# openSX70_LENS_BELLOWS_V51_20180120.net
KiCad netlist of a schematic drawn in EAGLE
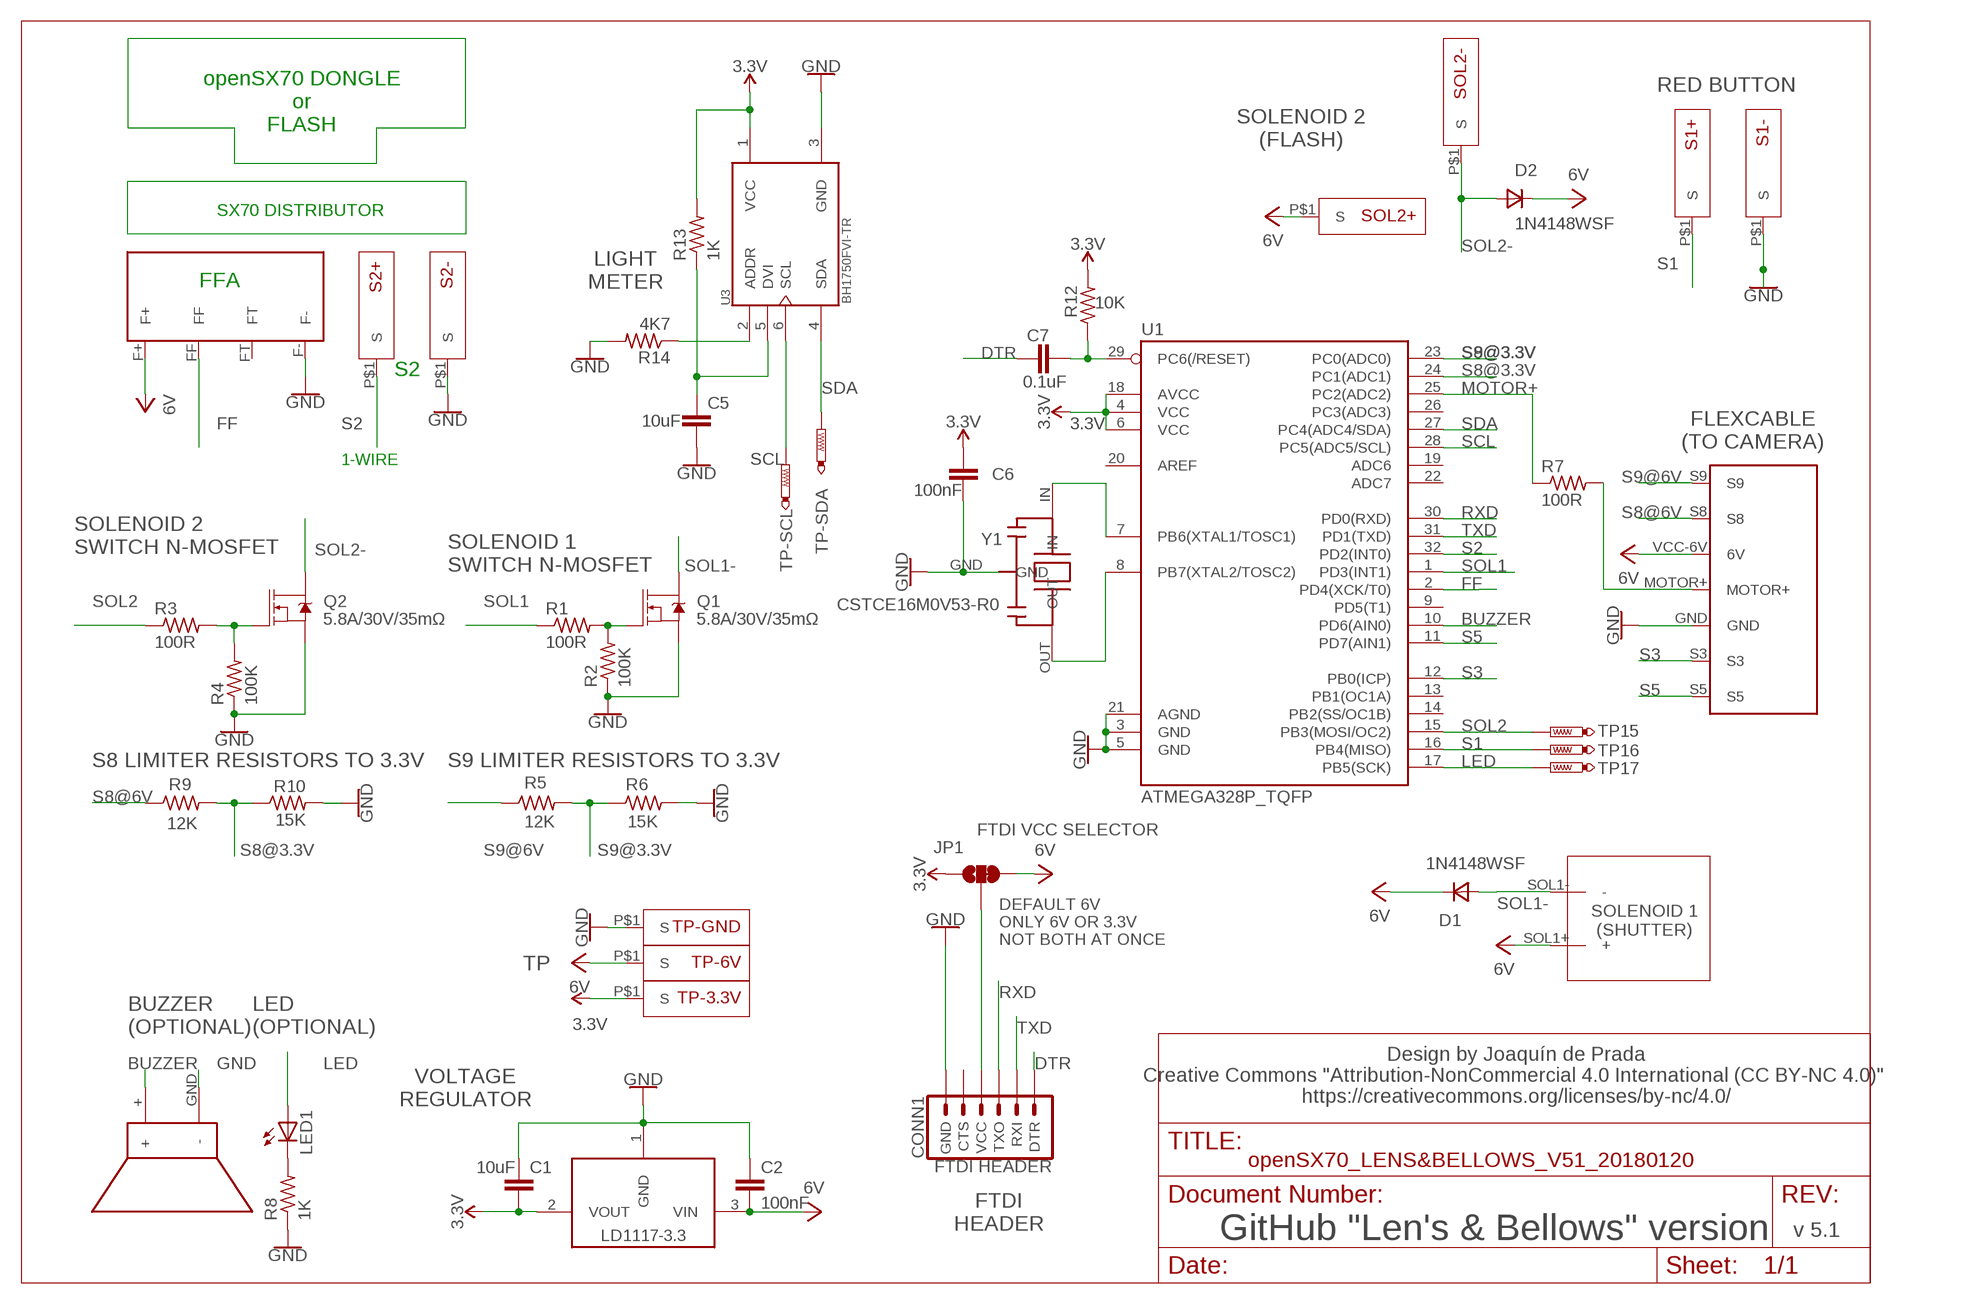
[diagram p0: schematic, sheet 1]

(export (version "E")
  (design (tool "Eeschema 10.0.6"))
  (components
    (comp (ref "BUZZ1")
      (value "CSET8-5G")
      (footprint "eagle-import:CSET8-5G_PACKAGE")
      (libsource (lib "eagle-import") (part "CSET8-5G"))
    )
    (comp (ref "C1")
      (value "10uF")
      (footprint "eagle-import:0603")
      (libsource (lib "eagle-import") (part "10UF-0603-6.3V-20%"))
    )
    (comp (ref "C2")
      (value "100nF")
      (footprint "eagle-import:C0603K")
      (libsource (lib "eagle-import") (part "C-EUC0603K"))
    )
    (comp (ref "C5")
      (value "10uF")
      (footprint "eagle-import:0603")
      (libsource (lib "eagle-import") (part "10UF-0603-6.3V-20%"))
    )
    (comp (ref "C6")
      (value "100nF")
      (footprint "eagle-import:C0603K")
      (libsource (lib "eagle-import") (part "C-EUC0603K"))
    )
    (comp (ref "C7")
      (value "0.1uF")
      (footprint "eagle-import:0603")
      (libsource (lib "eagle-import") (part "0.1UF-0603-25V-(+80/-20%)"))
    )
    (comp (ref "CONN1")
      (value "FTDI HEADER")
      (footprint "eagle-import:1X06")
      (libsource (lib "eagle-import") (part "6_PIN_SERIAL_TARGET"))
    )
    (comp (ref "D1")
      (value "1N4148WSF")
      (footprint "eagle-import:SOD323")
      (fields (field (name "MPN") "CDSOD323-T05C"))
      (libsource (lib "eagle-import") (part "DSOD323"))
    )
    (comp (ref "D2")
      (value "1N4148WSF")
      (footprint "eagle-import:SOD323")
      (fields (field (name "MPN") "CDSOD323-T05C"))
      (libsource (lib "eagle-import") (part "DSOD323"))
    )
    (comp (ref "JP1")
      (value "FTDI VCC SELECTOR")
      (footprint "eagle-import:SMT-JUMPER_3_1-NC_TRACE_SILK")
      (libsource (lib "eagle-import") (part "JUMPER-SMT_3_1-NC_TRACE_SILK"))
    )
    (comp (ref "LD11173.3V")
      (value "LD1117 3.3V")
      (footprint "eagle-import:SOT223")
      (fields (field (name "MF") "Advanced Monolithic Systems") (field (name "MP") "AMS1117-5.0"))
      (libsource (lib "eagle-import") (part "LD1117-3.3"))
    )
    (comp (ref "LED1")
      (value "LEDCHIPLED_0805")
      (footprint "eagle-import:CHIPLED_0805")
      (libsource (lib "eagle-import") (part "LEDCHIPLED_0805"))
    )
    (comp (ref "Q1")
      (value "5.8A/30V/35mΩ")
      (footprint "eagle-import:SOT23-3")
      (libsource (lib "eagle-import") (part "MOSFET-NCH-AO3404A"))
    )
    (comp (ref "Q2")
      (value "5.8A/30V/35mΩ")
      (footprint "eagle-import:SOT23-3")
      (libsource (lib "eagle-import") (part "MOSFET-NCH-AO3404A"))
    )
    (comp (ref "R1")
      (value "100R")
      (footprint "eagle-import:R0603")
      (libsource (lib "eagle-import") (part "R-US_R0603"))
    )
    (comp (ref "R2")
      (value "100K")
      (footprint "eagle-import:R0603")
      (libsource (lib "eagle-import") (part "R-US_R0603"))
    )
    (comp (ref "R3")
      (value "100R")
      (footprint "eagle-import:R0603")
      (libsource (lib "eagle-import") (part "R-US_R0603"))
    )
    (comp (ref "R4")
      (value "100K")
      (footprint "eagle-import:R0603")
      (libsource (lib "eagle-import") (part "R-US_R0603"))
    )
    (comp (ref "R5")
      (value "12K")
      (footprint "eagle-import:R0603")
      (libsource (lib "eagle-import") (part "R-US_R0603"))
    )
    (comp (ref "R6")
      (value "15K")
      (footprint "eagle-import:R0603")
      (libsource (lib "eagle-import") (part "R-US_R0603"))
    )
    (comp (ref "R7")
      (value "100R")
      (footprint "eagle-import:R0603")
      (libsource (lib "eagle-import") (part "R-US_R0603"))
    )
    (comp (ref "R8")
      (value "1K")
      (footprint "eagle-import:R0603")
      (libsource (lib "eagle-import") (part "R-US_R0603"))
    )
    (comp (ref "R9")
      (value "12K")
      (footprint "eagle-import:R0603")
      (libsource (lib "eagle-import") (part "R-US_R0603"))
    )
    (comp (ref "R10")
      (value "15K")
      (footprint "eagle-import:R0603")
      (libsource (lib "eagle-import") (part "R-US_R0603"))
    )
    (comp (ref "R12")
      (value "10K")
      (footprint "eagle-import:R0603")
      (libsource (lib "eagle-import") (part "R-US_R0603"))
    )
    (comp (ref "R13")
      (value "1K")
      (footprint "eagle-import:R0603")
      (libsource (lib "eagle-import") (part "R-US_R0603"))
    )
    (comp (ref "R14")
      (value "4K7")
      (footprint "eagle-import:R0603")
      (libsource (lib "eagle-import") (part "R-US_R0603"))
    )
    (comp (ref "S1+")
      (value "SX70-S-PAD-NEW")
      (footprint "eagle-import:SX70-S-PAD2")
      (libsource (lib "eagle-import") (part "SX70-S-PAD-NEW"))
    )
    (comp (ref "S1-")
      (value "SX70-S-PAD-NEW")
      (footprint "eagle-import:SX70-S-PAD2")
      (libsource (lib "eagle-import") (part "SX70-S-PAD-NEW"))
    )
    (comp (ref "S2+")
      (value "SX70-S-PAD-NEW")
      (footprint "eagle-import:SX70-S-PAD2")
      (libsource (lib "eagle-import") (part "SX70-S-PAD-NEW"))
    )
    (comp (ref "S2-")
      (value "SX70-S-PAD-NEW")
      (footprint "eagle-import:SX70-S-PAD2")
      (libsource (lib "eagle-import") (part "SX70-S-PAD-NEW"))
    )
    (comp (ref "SOL1")
      (value "SX70-SOLENOID1-2PADS")
      (footprint "eagle-import:SX70-SOLENOID1-2")
      (libsource (lib "eagle-import") (part "SX70-SOLENOID1-2PADS"))
    )
    (comp (ref "SOL2+")
      (value "SX70-S-PAD-NEW")
      (footprint "eagle-import:SX70-S-PAD2")
      (libsource (lib "eagle-import") (part "SX70-S-PAD-NEW"))
    )
    (comp (ref "SOL2-")
      (value "SX70-S-PAD-NEW")
      (footprint "eagle-import:SX70-S-PAD2")
      (libsource (lib "eagle-import") (part "SX70-S-PAD-NEW"))
    )
    (comp (ref "TP-3.3V")
      (value "SX70-S-PAD-NEW")
      (footprint "eagle-import:SX70-S-PAD2")
      (libsource (lib "eagle-import") (part "SX70-S-PAD-NEW"))
    )
    (comp (ref "TP-6V")
      (value "SX70-S-PAD-NEW")
      (footprint "eagle-import:SX70-S-PAD2")
      (libsource (lib "eagle-import") (part "SX70-S-PAD-NEW"))
    )
    (comp (ref "TP-GND")
      (value "SX70-S-PAD-NEW")
      (footprint "eagle-import:SX70-S-PAD2")
      (libsource (lib "eagle-import") (part "SX70-S-PAD-NEW"))
    )
    (comp (ref "TP-SCL")
      (value "PTR1TP08R")
      (footprint "eagle-import:TP08R")
      (libsource (lib "eagle-import") (part "PTR1TP08R"))
    )
    (comp (ref "TP-SDA")
      (value "PTR1TP08R")
      (footprint "eagle-import:TP08R")
      (libsource (lib "eagle-import") (part "PTR1TP08R"))
    )
    (comp (ref "TP15")
      (value "PTR1TP08R")
      (footprint "eagle-import:TP08R")
      (libsource (lib "eagle-import") (part "PTR1TP08R"))
    )
    (comp (ref "TP16")
      (value "PTR1TP08R")
      (footprint "eagle-import:TP08R")
      (libsource (lib "eagle-import") (part "PTR1TP08R"))
    )
    (comp (ref "TP17")
      (value "PTR1TP08R")
      (footprint "eagle-import:TP08R")
      (libsource (lib "eagle-import") (part "PTR1TP08R"))
    )
    (comp (ref "U$1")
      (value "SX70-7-PAD")
      (footprint "eagle-import:SX70-7-PAD")
      (libsource (lib "eagle-import") (part "SX70-7-PAD"))
    )
    (comp (ref "U$2")
      (value "FFA")
      (footprint "eagle-import:FFA-PAD-PACKAGE")
      (libsource (lib "eagle-import") (part "SX70-FFA-PAD"))
    )
    (comp (ref "U1")
      (value "ATMEGA328P_TQFP")
      (footprint "eagle-import:TQFP32-08")
      (libsource (lib "eagle-import") (part "ATMEGA328P_TQFP"))
    )
    (comp (ref "U3")
      (value "BH1750FVI-TR")
      (footprint "eagle-import:SOTFL50P300X75-6N")
      (fields (field (name "MF") "Rohm"))
      (libsource (lib "eagle-import") (part "BH1750FVI-TR"))
    )
    (comp (ref "Y1")
      (value "CSTCE16M0V53-R0")
      (footprint "eagle-import:CFP95P160X100-3N")
      (fields (field (name "MF") "Murata"))
      (libsource (lib "eagle-import") (part "CSTCE16M0V53-R0"))
    )
  )
  (nets
    (net (code "1") (name "/BUZZER") (class "Default")
      (node (ref "BUZZ1") (pin "+") (pinfunction "+_+") (pintype "bidirectional"))
      (node (ref "U1") (pin "10") (pinfunction "PD6(AIN0)_10") (pintype "bidirectional"))
    )
    (net (code "2") (name "/DTR") (class "Default")
      (node (ref "C7") (pin "1") (pinfunction "1_1") (pintype "passive"))
      (node (ref "CONN1") (pin "1") (pinfunction "DTR_1") (pintype "passive"))
    )
    (net (code "3") (name "/FF") (class "Default")
      (node (ref "U$2") (pin "FF") (pinfunction "FF_FF") (pintype "bidirectional"))
      (node (ref "U1") (pin "2") (pinfunction "PD4(XCK/T0)_2") (pintype "bidirectional"))
    )
    (net (code "4") (name "/LED") (class "Default")
      (node (ref "LED1") (pin "A") (pinfunction "A_A") (pintype "passive"))
      (node (ref "TP17") (pin "TP") (pinfunction "TP_TP") (pintype "input"))
      (node (ref "U1") (pin "17") (pinfunction "PB5(SCK)_17") (pintype "bidirectional"))
    )
    (net (code "5") (name "/MOTOR+") (class "Default")
      (node (ref "R7") (pin "1") (pinfunction "1_1") (pintype "passive"))
      (node (ref "U1") (pin "25") (pinfunction "PC2(ADC2)_25") (pintype "bidirectional"))
    )
    (net (code "6") (name "/RXD") (class "Default")
      (node (ref "CONN1") (pin "3") (pinfunction "TXO_3") (pintype "passive"))
      (node (ref "U1") (pin "30") (pinfunction "PD0(RXD)_30") (pintype "bidirectional"))
    )
    (net (code "7") (name "/S1") (class "Default")
      (node (ref "S1+") (pin "P$1") (pinfunction "S_P$1") (pintype "bidirectional"))
      (node (ref "TP16") (pin "TP") (pinfunction "TP_TP") (pintype "input"))
      (node (ref "U1") (pin "16") (pinfunction "PB4(MISO)_16") (pintype "bidirectional"))
    )
    (net (code "8") (name "/S2") (class "Default")
      (node (ref "S2+") (pin "P$1") (pinfunction "S_P$1") (pintype "bidirectional"))
      (node (ref "U1") (pin "32") (pinfunction "PD2(INT0)_32") (pintype "bidirectional"))
    )
    (net (code "9") (name "/S3") (class "Default")
      (node (ref "U$1") (pin "S3") (pinfunction "S3_S3") (pintype "bidirectional"))
      (node (ref "U1") (pin "12") (pinfunction "PB0(ICP)_12") (pintype "bidirectional"))
    )
    (net (code "10") (name "/S5") (class "Default")
      (node (ref "U$1") (pin "S5") (pinfunction "S5_S5") (pintype "bidirectional"))
      (node (ref "U1") (pin "11") (pinfunction "PD7(AIN1)_11") (pintype "bidirectional"))
    )
    (net (code "11") (name "/S8@3.3V") (class "Default")
      (node (ref "R10") (pin "1") (pinfunction "1_1") (pintype "passive"))
      (node (ref "R9") (pin "2") (pinfunction "2_2") (pintype "passive"))
      (node (ref "U1") (pin "24") (pinfunction "PC1(ADC1)_24") (pintype "bidirectional"))
    )
    (net (code "12") (name "/S8@6V") (class "Default")
      (node (ref "R9") (pin "1") (pinfunction "1_1") (pintype "passive"))
      (node (ref "U$1") (pin "S8") (pinfunction "S8_S8") (pintype "bidirectional"))
    )
    (net (code "13") (name "/S9@3.3V") (class "Default")
      (node (ref "R5") (pin "2") (pinfunction "2_2") (pintype "passive"))
      (node (ref "R6") (pin "1") (pinfunction "1_1") (pintype "passive"))
      (node (ref "U1") (pin "23") (pinfunction "PC0(ADC0)_23") (pintype "bidirectional"))
    )
    (net (code "14") (name "/S9@6V") (class "Default")
      (node (ref "R5") (pin "1") (pinfunction "1_1") (pintype "passive"))
      (node (ref "U$1") (pin "S9") (pinfunction "S9_S9") (pintype "bidirectional"))
    )
    (net (code "15") (name "/SCL") (class "Default")
      (node (ref "TP-SCL") (pin "TP") (pinfunction "TP_TP") (pintype "input"))
      (node (ref "U1") (pin "28") (pinfunction "PC5(ADC5/SCL)_28") (pintype "bidirectional"))
      (node (ref "U3") (pin "6") (pinfunction "SCL_6") (pintype "input"))
    )
    (net (code "16") (name "/SDA") (class "Default")
      (node (ref "TP-SDA") (pin "TP") (pinfunction "TP_TP") (pintype "input"))
      (node (ref "U1") (pin "27") (pinfunction "PC4(ADC4/SDA)_27") (pintype "bidirectional"))
      (node (ref "U3") (pin "4") (pinfunction "SDA_4") (pintype "bidirectional"))
    )
    (net (code "17") (name "/SOL1") (class "Default")
      (node (ref "R1") (pin "1") (pinfunction "1_1") (pintype "passive"))
      (node (ref "U1") (pin "1") (pinfunction "PD3(INT1)_1") (pintype "bidirectional"))
    )
    (net (code "18") (name "/SOL1-") (class "Default")
      (node (ref "D1") (pin "2") (pinfunction "A_2") (pintype "passive"))
      (node (ref "Q1") (pin "3") (pinfunction "D_3") (pintype "bidirectional"))
      (node (ref "SOL1") (pin "SOL1-") (pinfunction "-_SOL1-") (pintype "bidirectional"))
    )
    (net (code "19") (name "/SOL2") (class "Default")
      (node (ref "R3") (pin "1") (pinfunction "1_1") (pintype "passive"))
      (node (ref "TP15") (pin "TP") (pinfunction "TP_TP") (pintype "input"))
      (node (ref "U1") (pin "15") (pinfunction "PB3(MOSI/OC2)_15") (pintype "bidirectional"))
    )
    (net (code "20") (name "/SOL2-") (class "Default")
      (node (ref "D2") (pin "2") (pinfunction "A_2") (pintype "passive"))
      (node (ref "Q2") (pin "3") (pinfunction "D_3") (pintype "bidirectional"))
      (node (ref "SOL2-") (pin "P$1") (pinfunction "S_P$1") (pintype "bidirectional"))
    )
    (net (code "21") (name "/TXD") (class "Default")
      (node (ref "CONN1") (pin "2") (pinfunction "RXI_2") (pintype "passive"))
      (node (ref "U1") (pin "31") (pinfunction "PD1(TXD)_31") (pintype "bidirectional"))
    )
    (net (code "22") (name "3.3V") (class "Default")
      (node (ref "C1") (pin "2") (pinfunction "2_2") (pintype "passive"))
      (node (ref "C6") (pin "1") (pinfunction "1_1") (pintype "passive"))
      (node (ref "JP1") (pin "1") (pinfunction "1_1") (pintype "passive"))
      (node (ref "LD11173.3V") (pin "2") (pinfunction "VOUT_2") (pintype "bidirectional"))
      (node (ref "R12") (pin "2") (pinfunction "2_2") (pintype "passive"))
      (node (ref "R13") (pin "2") (pinfunction "2_2") (pintype "passive"))
      (node (ref "TP-3.3V") (pin "P$1") (pinfunction "S_P$1") (pintype "bidirectional"))
      (node (ref "U1") (pin "18") (pinfunction "AVCC_18") (pintype "bidirectional"))
      (node (ref "U1") (pin "4") (pinfunction "VCC_4") (pintype "bidirectional"))
      (node (ref "U1") (pin "6") (pinfunction "VCC_6") (pintype "bidirectional"))
      (node (ref "U3") (pin "1") (pinfunction "VCC_1") (pintype "power_in"))
    )
    (net (code "23") (name "6V") (class "Default")
      (node (ref "C2") (pin "2") (pinfunction "2_2") (pintype "passive"))
      (node (ref "D1") (pin "1") (pinfunction "C_1") (pintype "passive"))
      (node (ref "D2") (pin "1") (pinfunction "C_1") (pintype "passive"))
      (node (ref "JP1") (pin "3") (pinfunction "3_3") (pintype "passive"))
      (node (ref "LD11173.3V") (pin "3") (pinfunction "VIN_3") (pintype "bidirectional"))
      (node (ref "SOL1") (pin "SOL1+") (pinfunction "+_SOL1+") (pintype "bidirectional"))
      (node (ref "SOL2+") (pin "P$1") (pinfunction "S_P$1") (pintype "bidirectional"))
      (node (ref "TP-6V") (pin "P$1") (pinfunction "S_P$1") (pintype "bidirectional"))
      (node (ref "U$1") (pin "VCC-6V") (pinfunction "6V_VCC-6V") (pintype "bidirectional"))
      (node (ref "U$2") (pin "F+") (pinfunction "F+_F+") (pintype "bidirectional"))
    )
    (net (code "24") (name "GND") (class "Default")
      (node (ref "BUZZ1") (pin "GND") (pinfunction "-_GND") (pintype "bidirectional"))
      (node (ref "C1") (pin "1") (pinfunction "1_1") (pintype "passive"))
      (node (ref "C2") (pin "1") (pinfunction "1_1") (pintype "passive"))
      (node (ref "C5") (pin "2") (pinfunction "2_2") (pintype "passive"))
      (node (ref "C6") (pin "2") (pinfunction "2_2") (pintype "passive"))
      (node (ref "CONN1") (pin "6") (pinfunction "GND_6") (pintype "passive"))
      (node (ref "LD11173.3V") (pin "1") (pinfunction "GND_1") (pintype "bidirectional"))
      (node (ref "Q1") (pin "2") (pinfunction "S_2") (pintype "bidirectional"))
      (node (ref "Q2") (pin "2") (pinfunction "S_2") (pintype "bidirectional"))
      (node (ref "R10") (pin "2") (pinfunction "2_2") (pintype "passive"))
      (node (ref "R14") (pin "2") (pinfunction "2_2") (pintype "passive"))
      (node (ref "R2") (pin "1") (pinfunction "1_1") (pintype "passive"))
      (node (ref "R4") (pin "1") (pinfunction "1_1") (pintype "passive"))
      (node (ref "R6") (pin "2") (pinfunction "2_2") (pintype "passive"))
      (node (ref "R8") (pin "1") (pinfunction "1_1") (pintype "passive"))
      (node (ref "S1-") (pin "P$1") (pinfunction "S_P$1") (pintype "bidirectional"))
      (node (ref "S2-") (pin "P$1") (pinfunction "S_P$1") (pintype "bidirectional"))
      (node (ref "TP-GND") (pin "P$1") (pinfunction "S_P$1") (pintype "bidirectional"))
      (node (ref "U$1") (pin "GND") (pinfunction "GND_GND") (pintype "bidirectional"))
      (node (ref "U$2") (pin "F-") (pinfunction "F-_F-") (pintype "bidirectional"))
      (node (ref "U1") (pin "21") (pinfunction "AGND_21") (pintype "bidirectional"))
      (node (ref "U1") (pin "3") (pinfunction "GND_3") (pintype "bidirectional"))
      (node (ref "U1") (pin "5") (pinfunction "GND_5") (pintype "bidirectional"))
      (node (ref "U3") (pin "3") (pinfunction "GND_3") (pintype "power_in"))
      (node (ref "Y1") (pin "GND") (pinfunction "GND_GND") (pintype "passive"))
    )
    (net (code "25") (name "Net-(CONN1-VCC)") (class "Default")
      (node (ref "CONN1") (pin "4") (pinfunction "VCC_4") (pintype "passive"))
      (node (ref "JP1") (pin "2") (pinfunction "2_2") (pintype "passive"))
    )
    (net (code "26") (name "Net-(LED1-PadC)") (class "Default")
      (node (ref "LED1") (pin "C") (pinfunction "C_C") (pintype "passive"))
      (node (ref "R8") (pin "2") (pinfunction "2_2") (pintype "passive"))
    )
    (net (code "27") (name "Net-(Q1-G)") (class "Default")
      (node (ref "Q1") (pin "1") (pinfunction "G_1") (pintype "bidirectional"))
      (node (ref "R1") (pin "2") (pinfunction "2_2") (pintype "passive"))
      (node (ref "R2") (pin "2") (pinfunction "2_2") (pintype "passive"))
    )
    (net (code "28") (name "Net-(Q2-G)") (class "Default")
      (node (ref "Q2") (pin "1") (pinfunction "G_1") (pintype "bidirectional"))
      (node (ref "R3") (pin "2") (pinfunction "2_2") (pintype "passive"))
      (node (ref "R4") (pin "2") (pinfunction "2_2") (pintype "passive"))
    )
    (net (code "29") (name "Net-(R7-Pad2)") (class "Default")
      (node (ref "R7") (pin "2") (pinfunction "2_2") (pintype "passive"))
      (node (ref "U$1") (pin "MOTOR+") (pinfunction "MOTOR+_MOTOR+") (pintype "bidirectional"))
    )
    (net (code "30") (name "Net-(U1-PB6(XTAL1{slash}TOSC1))") (class "Default")
      (node (ref "U1") (pin "7") (pinfunction "PB6(XTAL1/TOSC1)_7") (pintype "bidirectional"))
      (node (ref "Y1") (pin "IN") (pinfunction "IN_IN") (pintype "input"))
    )
    (net (code "31") (name "Net-(U1-PB7(XTAL2{slash}TOSC2))") (class "Default")
      (node (ref "U1") (pin "8") (pinfunction "PB7(XTAL2/TOSC2)_8") (pintype "bidirectional"))
      (node (ref "Y1") (pin "OUT") (pinfunction "OUT_OUT") (pintype "output"))
    )
    (net (code "32") (name "Net-(U1-PC6({slash}RESET))") (class "Default")
      (node (ref "C7") (pin "2") (pinfunction "2_2") (pintype "passive"))
      (node (ref "R12") (pin "1") (pinfunction "1_1") (pintype "passive"))
      (node (ref "U1") (pin "29") (pinfunction "PC6(/RESET)_29") (pintype "bidirectional"))
    )
    (net (code "33") (name "Net-(U3-ADDR)") (class "Default")
      (node (ref "R14") (pin "1") (pinfunction "1_1") (pintype "passive"))
      (node (ref "U3") (pin "2") (pinfunction "ADDR_2") (pintype "input"))
    )
    (net (code "34") (name "Net-(U3-DVI)") (class "Default")
      (node (ref "C5") (pin "1") (pinfunction "1_1") (pintype "passive"))
      (node (ref "R13") (pin "1") (pinfunction "1_1") (pintype "passive"))
      (node (ref "U3") (pin "5") (pinfunction "DVI_5") (pintype "input"))
    )
    (net (code "35") (name "unconnected-(CONN1-CTS-Pad5)") (class "Default")
      (node (ref "CONN1") (pin "5") (pinfunction "CTS_5") (pintype "passive"))
    )
    (net (code "36") (name "unconnected-(U$2-PadFT)") (class "Default")
      (node (ref "U$2") (pin "FT") (pinfunction "FT_FT") (pintype "bidirectional"))
    )
    (net (code "37") (name "unconnected-(U1-ADC6-Pad19)") (class "Default")
      (node (ref "U1") (pin "19") (pinfunction "ADC6_19") (pintype "bidirectional"))
    )
    (net (code "38") (name "unconnected-(U1-ADC7-Pad22)") (class "Default")
      (node (ref "U1") (pin "22") (pinfunction "ADC7_22") (pintype "bidirectional"))
    )
    (net (code "39") (name "unconnected-(U1-AREF-Pad20)") (class "Default")
      (node (ref "U1") (pin "20") (pinfunction "AREF_20") (pintype "bidirectional"))
    )
    (net (code "40") (name "unconnected-(U1-PB1(OC1A)-Pad13)") (class "Default")
      (node (ref "U1") (pin "13") (pinfunction "PB1(OC1A)_13") (pintype "bidirectional"))
    )
    (net (code "41") (name "unconnected-(U1-PB2(SS{slash}OC1B)-Pad14)") (class "Default")
      (node (ref "U1") (pin "14") (pinfunction "PB2(SS/OC1B)_14") (pintype "bidirectional"))
    )
    (net (code "42") (name "unconnected-(U1-PC3(ADC3)-Pad26)") (class "Default")
      (node (ref "U1") (pin "26") (pinfunction "PC3(ADC3)_26") (pintype "bidirectional"))
    )
    (net (code "43") (name "unconnected-(U1-PD5(T1)-Pad9)") (class "Default")
      (node (ref "U1") (pin "9") (pinfunction "PD5(T1)_9") (pintype "bidirectional"))
    )
  )
)
